# Multi-Function_Expander.net
KiCad netlist of a schematic drawn in Altium Designer
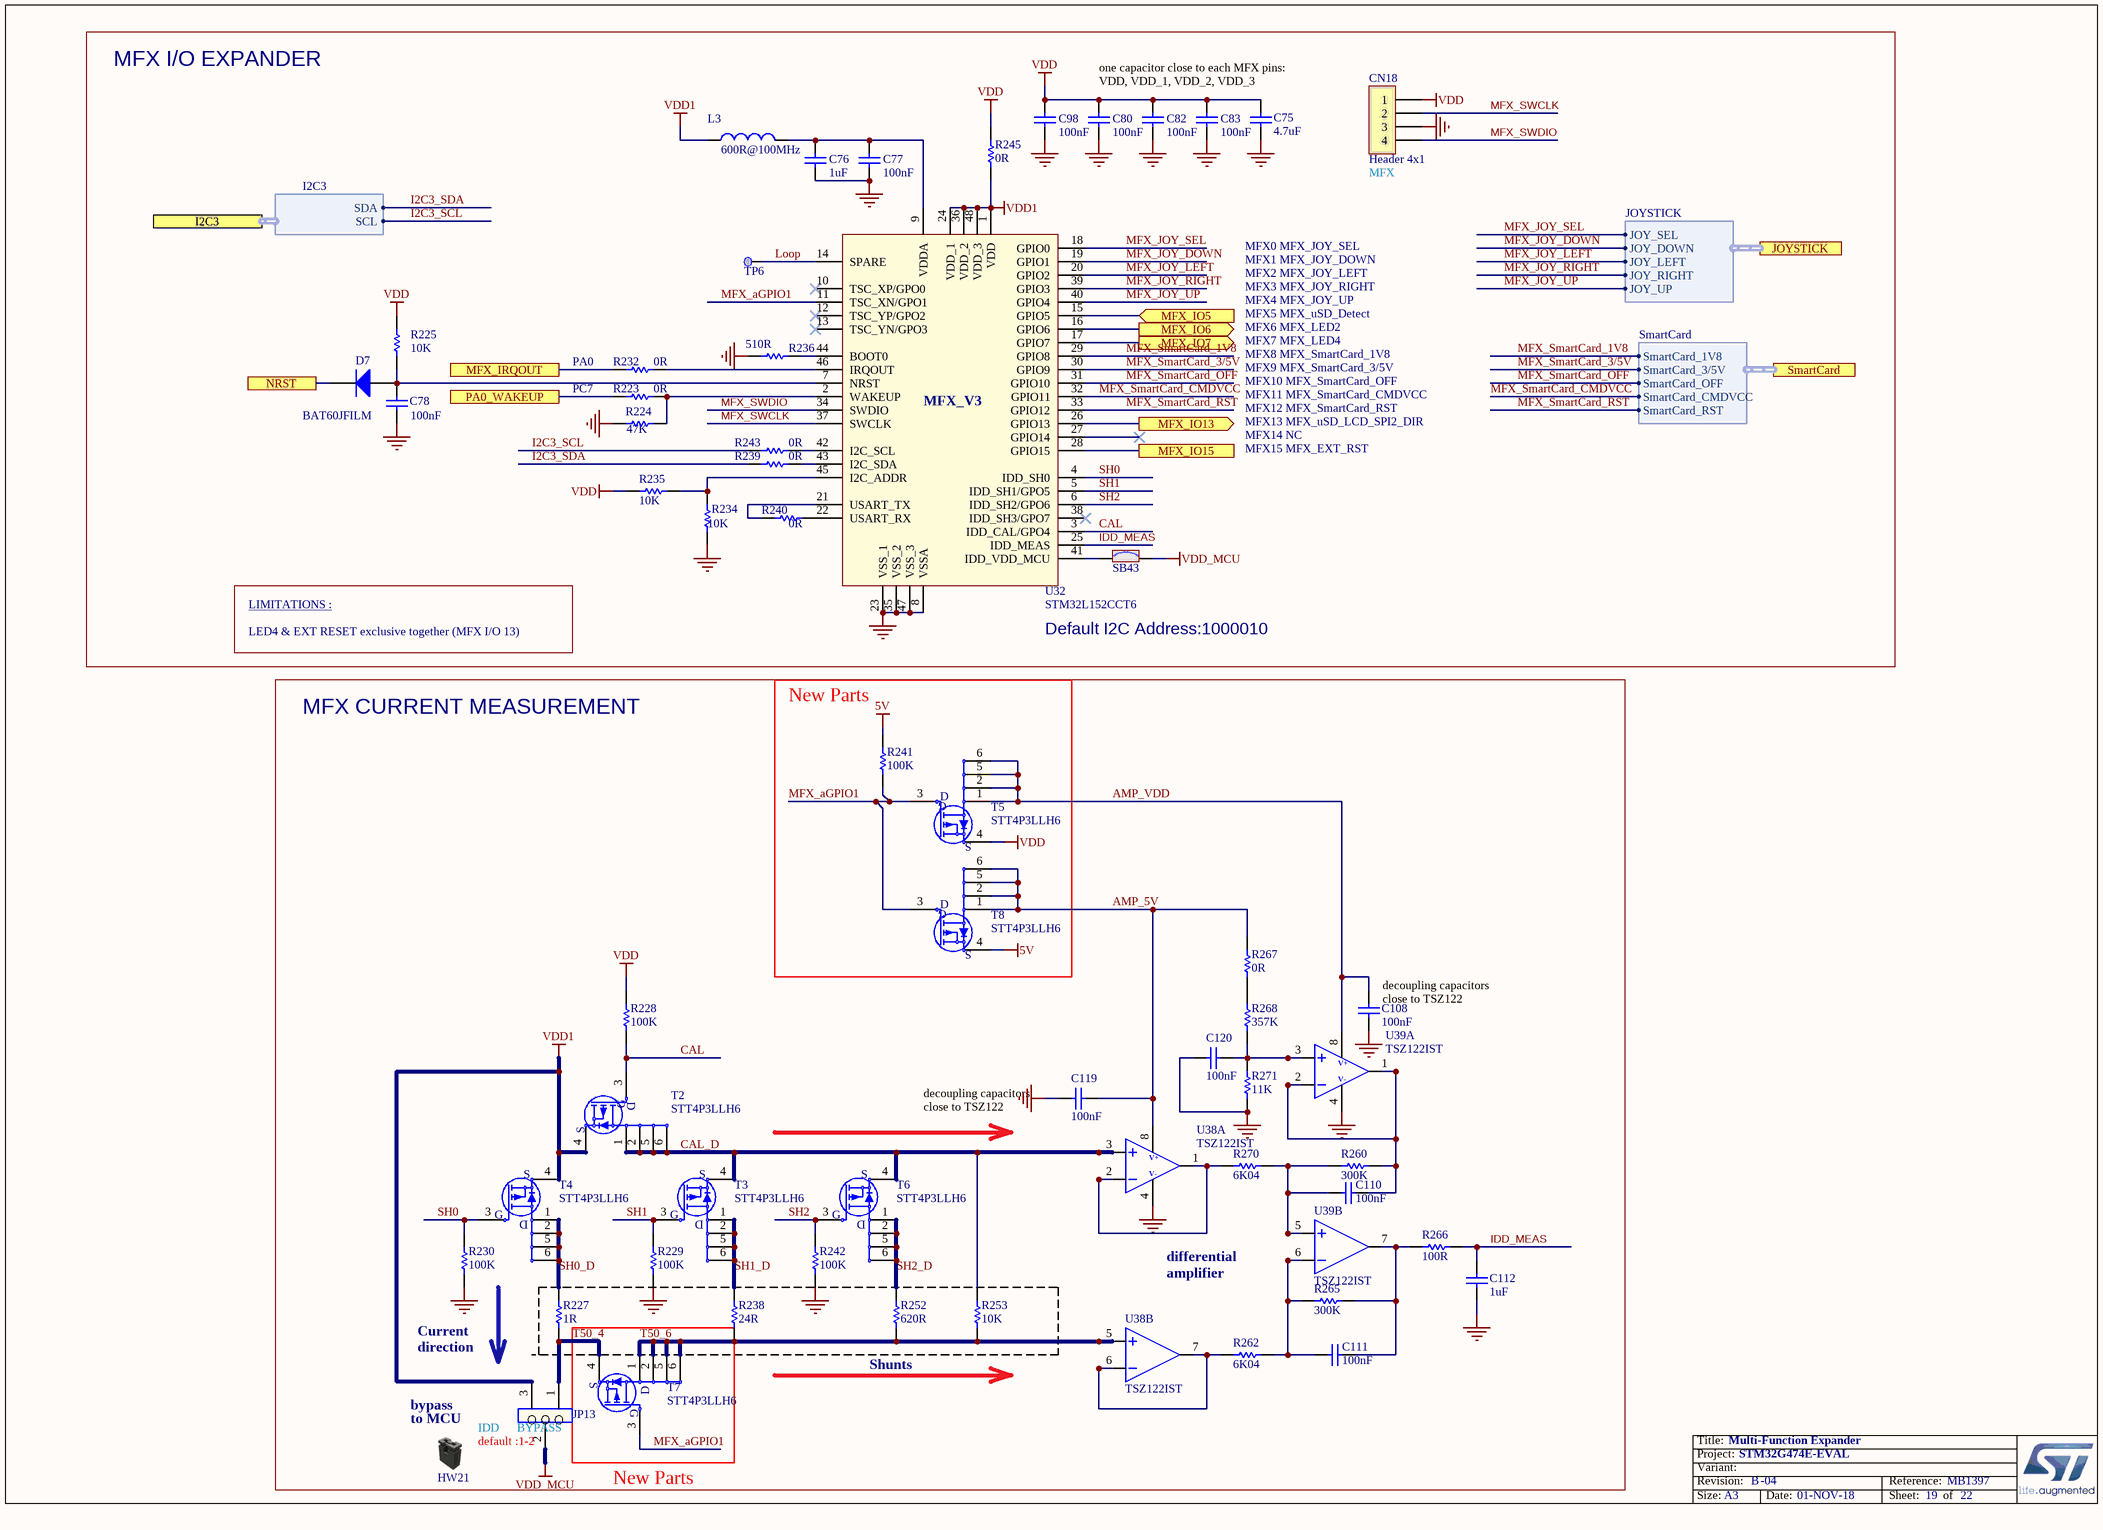
[diagram p0: Multi-Function Expander.SchDoc]

(export (version "E")
  (design (tool "Eeschema 10.0.6"))
  (components
    (comp (ref "C75")
      (value "4.7uF")
      (footprint "C0603")
      (description "Capacitor, MLCC, 4.7uF, 16V, X5R, 10%, 0603, T=0.8mm")
      (fields
        (field (name "INTERNAL_PART_NUMBER") "MCD-00009")
        (field (name "MANUFACTURER_PART_NUMBER") "CC0603KRX5R7BB475")
        (field (name "PROVIDED_BY") "SUBCO")
      )
      (libsource (lib "MCD_PARTS_database") (part "Capacitor"))
    )
    (comp (ref "C76")
      (value "1uF")
      (footprint "C0603")
      (description "Capacitor, MLCC, 1uF, 16V, X5R, 10%, 0603, T=0,8mm")
      (fields
        (field (name "INTERNAL_PART_NUMBER") "MCD-00010")
        (field (name "MANUFACTURER_PART_NUMBER") "CC0603KRX5R7BB105")
        (field (name "PROVIDED_BY") "SUBCO")
      )
      (libsource (lib "MCD_PARTS_database") (part "Capacitor"))
    )
    (comp (ref "C77")
      (value "100nF")
      (footprint "C0402")
      (description "Capacitor, MLCC, 100nF, 16V, X7R, 10%, 0402, T=0.5mm")
      (fields
        (field (name "INTERNAL_PART_NUMBER") "MCD-00006")
        (field (name "MANUFACTURER_PART_NUMBER") "CC0402KRX7R7BB104")
        (field (name "PROVIDED_BY") "SUBCO")
      )
      (libsource (lib "MCD_PARTS_database") (part "Capacitor"))
    )
    (comp (ref "C78")
      (value "100nF")
      (footprint "C0402")
      (description "Capacitor, MLCC, 100nF, 16V, X7R, 10%, 0402, T=0.5mm")
      (fields
        (field (name "INTERNAL_PART_NUMBER") "MCD-00006")
        (field (name "MANUFACTURER_PART_NUMBER") "CC0402KRX7R7BB104")
        (field (name "PROVIDED_BY") "SUBCO")
      )
      (libsource (lib "MCD_PARTS_database") (part "Capacitor"))
    )
    (comp (ref "C80")
      (value "100nF")
      (footprint "C0402")
      (description "Capacitor, MLCC, 100nF, 16V, X7R, 10%, 0402, T=0.5mm")
      (fields
        (field (name "INTERNAL_PART_NUMBER") "MCD-00006")
        (field (name "MANUFACTURER_PART_NUMBER") "CC0402KRX7R7BB104")
        (field (name "PROVIDED_BY") "SUBCO")
      )
      (libsource (lib "MCD_PARTS_database") (part "Capacitor"))
    )
    (comp (ref "C82")
      (value "100nF")
      (footprint "C0402")
      (description "Capacitor, MLCC, 100nF, 16V, X7R, 10%, 0402, T=0.5mm")
      (fields
        (field (name "INTERNAL_PART_NUMBER") "MCD-00006")
        (field (name "MANUFACTURER_PART_NUMBER") "CC0402KRX7R7BB104")
        (field (name "PROVIDED_BY") "SUBCO")
      )
      (libsource (lib "MCD_PARTS_database") (part "Capacitor"))
    )
    (comp (ref "C83")
      (value "100nF")
      (footprint "C0402")
      (description "Capacitor, MLCC, 100nF, 16V, X7R, 10%, 0402, T=0.5mm")
      (fields
        (field (name "INTERNAL_PART_NUMBER") "MCD-00006")
        (field (name "MANUFACTURER_PART_NUMBER") "CC0402KRX7R7BB104")
        (field (name "PROVIDED_BY") "SUBCO")
      )
      (libsource (lib "MCD_PARTS_database") (part "Capacitor"))
    )
    (comp (ref "C98")
      (value "100nF")
      (footprint "C0402")
      (description "Capacitor, MLCC, 100nF, 16V, X7R, 10%, 0402, T=0.5mm")
      (fields
        (field (name "INTERNAL_PART_NUMBER") "MCD-00006")
        (field (name "MANUFACTURER_PART_NUMBER") "CC0402KRX7R7BB104")
        (field (name "PROVIDED_BY") "SUBCO")
      )
      (libsource (lib "MCD_PARTS_database") (part "Capacitor"))
    )
    (comp (ref "C108")
      (value "100nF")
      (footprint "C0603")
      (description "Capacitor, MLCC, 100nF, 16V, X7R, 10%, 0603, T=0,8mm")
      (fields
        (field (name "INTERNAL_PART_NUMBER") "MCD-00211")
        (field (name "MANUFACTURER_PART_NUMBER") "CC0603KRX7R7BB104")
        (field (name "PROVIDED_BY") "SUBCO")
      )
      (libsource (lib "MCD_PARTS_database") (part "Capacitor"))
    )
    (comp (ref "C110")
      (value "100nF")
      (footprint "C0603")
      (description "Capacitor, MLCC, 100nF, 16V, X7R, 10%, 0603, T=0,8mm")
      (fields
        (field (name "INTERNAL_PART_NUMBER") "MCD-00211")
        (field (name "MANUFACTURER_PART_NUMBER") "CC0603KRX7R7BB104")
        (field (name "PROVIDED_BY") "SUBCO")
      )
      (libsource (lib "MCD_PARTS_database") (part "Capacitor"))
    )
    (comp (ref "C111")
      (value "100nF")
      (footprint "C0603")
      (description "Capacitor, MLCC, 100nF, 16V, X7R, 10%, 0603, T=0,8mm")
      (fields
        (field (name "INTERNAL_PART_NUMBER") "MCD-00211")
        (field (name "MANUFACTURER_PART_NUMBER") "CC0603KRX7R7BB104")
        (field (name "PROVIDED_BY") "SUBCO")
      )
      (libsource (lib "MCD_PARTS_database") (part "Capacitor"))
    )
    (comp (ref "C112")
      (value "1uF")
      (footprint "C0603")
      (description "Capacitor, MLCC, 1uF, 16V, X5R, 10%, 0603, T=0,8mm")
      (fields
        (field (name "INTERNAL_PART_NUMBER") "MCD-00010")
        (field (name "MANUFACTURER_PART_NUMBER") "CC0603KRX5R7BB105")
        (field (name "PROVIDED_BY") "SUBCO")
      )
      (libsource (lib "MCD_PARTS_database") (part "Capacitor"))
    )
    (comp (ref "C119")
      (value "100nF")
      (footprint "C0603")
      (description "Capacitor, MLCC, 100nF, 16V, X7R, 10%, 0603, T=0,8mm")
      (fields
        (field (name "INTERNAL_PART_NUMBER") "MCD-00211")
        (field (name "MANUFACTURER_PART_NUMBER") "CC0603KRX7R7BB104")
        (field (name "PROVIDED_BY") "SUBCO")
      )
      (libsource (lib "MCD_PARTS_database") (part "Capacitor"))
    )
    (comp (ref "C120")
      (value "100nF")
      (footprint "C0603")
      (description "Capacitor, MLCC, 100nF, 16V, X7R, 10%, 0603, T=0,8mm")
      (fields
        (field (name "INTERNAL_PART_NUMBER") "MCD-00211")
        (field (name "MANUFACTURER_PART_NUMBER") "CC0603KRX7R7BB104")
        (field (name "PROVIDED_BY") "SUBCO")
      )
      (libsource (lib "MCD_PARTS_database") (part "Capacitor"))
    )
    (comp (ref "CN18")
      (value "Header 4x1")
      (footprint "CON_SAMTEC_TSW-104-07-G-S")
      (description "Header, 4x1, 2,54mm, VR, TH, Height 5.84mm/2.54mm")
      (fields
        (field (name "INTERNAL_PART_NUMBER") "MCD-00029")
        (field (name "MANUFACTURER_PART_NUMBER") "TSW-104-07-x-S")
        (field (name "PROVIDED_BY") "SUBCO")
      )
      (libsource (lib "MCD_PARTS_database") (part "Header 4x1"))
    )
    (comp (ref "D7")
      (value "BAT60JFILM")
      (footprint "DIO_SOD323")
      (fields
        (field (name "INTERNAL_PART_NUMBER") "MCD-00034")
        (field (name "MANUFACTURER") "STMICROELECTRONICS")
        (field (name "BMS_PART_NUMBER") "9151097")
        (field (name "PROVIDED_BY") "SUBCO with ST control")
      )
      (libsource (lib "MCD_PARTS_database") (part "BAT60JFILM"))
    )
    (comp (ref "HW21")
      (value "Shunt Black 2.54mm")
      (description "SHUNT 2.54mm BLACK")
      (fields
        (field (name "INTERNAL_PART_NUMBER") "MCD-00043")
        (field (name "MANUFACTURER_PART_NUMBER") "SNT-100-BK-G")
        (field (name "PROVIDED_BY") "SUBCO")
      )
      (libsource (lib "MCD_PARTS_database") (part "Shunt Black 2.54mm"))
    )
    (comp (ref "JP13")
      (value "Jumper_Header 3x1")
      (footprint "CON_SAMTEC_TSW-103-07-F-S")
      (description "Header, 3x1, 2,54mm, VR, TH, Height 5.84mm/2.54mm")
      (fields
        (field (name "INTERNAL_PART_NUMBER") "MCD-00111")
        (field (name "MANUFACTURER_PART_NUMBER") "TSW-103-07-F-S")
        (field (name "PROVIDED_BY") "SUBCO")
      )
      (libsource (lib "MCD_PARTS_database") (part "Jumper_Header 3x1"))
    )
    (comp (ref "L3")
      (value "600R@100MHz")
      (footprint "L0603")
      (description "SMD Chip ferrite bead, 600R@100MHz +/-25%, 350mA, 500mohm DC, 0603, T=0.8mm")
      (fields
        (field (name "INTERNAL_PART_NUMBER") "MCD-00047")
        (field (name "MANUFACTURER_PART_NUMBER") "FCM1608KF-601T03")
        (field (name "PROVIDED_BY") "SUBCO")
      )
      (libsource (lib "MCD_PARTS_database") (part "BEAD"))
    )
    (comp (ref "R223")
      (value "0R")
      (footprint "R0603")
      (description "Resistor,0R,0603,5%,1/10W")
      (fields
        (field (name "INTERNAL_PART_NUMBER") "MCD-00056")
        (field (name "MANUFACTURER_PART_NUMBER") "RC0603JR-070RL")
        (field (name "PROVIDED_BY") "SUBCO")
      )
      (libsource (lib "MCD_PARTS_database") (part "Resistor"))
    )
    (comp (ref "R224")
      (value "47K")
      (footprint "R0402")
      (description "Resistor,47K,0402,1%,1/16W")
      (fields
        (field (name "INTERNAL_PART_NUMBER") "MCD-00063")
        (field (name "MANUFACTURER_PART_NUMBER") "RC0402FR-0747KL")
        (field (name "PROVIDED_BY") "SUBCO")
      )
      (libsource (lib "MCD_PARTS_database") (part "Resistor"))
    )
    (comp (ref "R225")
      (value "10K")
      (footprint "R0402")
      (description "Resistor,10K,0402,1%,1/16W")
      (fields
        (field (name "INTERNAL_PART_NUMBER") "MCD-00053")
        (field (name "MANUFACTURER_PART_NUMBER") "RC0402FR-0710KL")
        (field (name "PROVIDED_BY") "SUBCO")
      )
      (libsource (lib "MCD_PARTS_database") (part "Resistor"))
    )
    (comp (ref "R227")
      (value "1R")
      (footprint "R0805")
      (description "Resistor, 1R, 0805, 1%, 1/8W")
      (fields
        (field (name "INTERNAL_PART_NUMBER") "MCD-00323")
        (field (name "MANUFACTURER_PART_NUMBER") "RC0805FR-071RL")
        (field (name "PROVIDED_BY") "SUBCO")
      )
      (libsource (lib "MCD_PARTS_database") (part "Resistor"))
    )
    (comp (ref "R228")
      (value "100K")
      (footprint "R0603")
      (description "Resistor,100K,0603,1%,1/10W")
      (fields
        (field (name "INTERNAL_PART_NUMBER") "MCD-00223")
        (field (name "MANUFACTURER_PART_NUMBER") "RC0603FR-07100KL")
        (field (name "PROVIDED_BY") "SUBCO")
      )
      (libsource (lib "MCD_PARTS_database") (part "Resistor"))
    )
    (comp (ref "R229")
      (value "100K")
      (footprint "R0603")
      (description "Resistor,100K,0603,1%,1/10W")
      (fields
        (field (name "INTERNAL_PART_NUMBER") "MCD-00223")
        (field (name "MANUFACTURER_PART_NUMBER") "RC0603FR-07100KL")
        (field (name "PROVIDED_BY") "SUBCO")
      )
      (libsource (lib "MCD_PARTS_database") (part "Resistor"))
    )
    (comp (ref "R230")
      (value "100K")
      (footprint "R0603")
      (description "Resistor,100K,0603,1%,1/10W")
      (fields
        (field (name "INTERNAL_PART_NUMBER") "MCD-00223")
        (field (name "MANUFACTURER_PART_NUMBER") "RC0603FR-07100KL")
        (field (name "PROVIDED_BY") "SUBCO")
      )
      (libsource (lib "MCD_PARTS_database") (part "Resistor"))
    )
    (comp (ref "R232")
      (value "0R")
      (footprint "R0603")
      (description "Resistor,0R,0603,5%,1/10W")
      (fields
        (field (name "INTERNAL_PART_NUMBER") "MCD-00056")
        (field (name "MANUFACTURER_PART_NUMBER") "RC0603JR-070RL")
        (field (name "PROVIDED_BY") "SUBCO")
      )
      (libsource (lib "MCD_PARTS_database") (part "Resistor"))
    )
    (comp (ref "R234")
      (value "10K")
      (footprint "R0402")
      (description "Resistor,10K,0402,1%,1/16W")
      (fields
        (field (name "INTERNAL_PART_NUMBER") "MCD-00053")
        (field (name "MANUFACTURER_PART_NUMBER") "RC0402FR-0710KL")
        (field (name "PROVIDED_BY") "SUBCO")
      )
      (libsource (lib "MCD_PARTS_database") (part "Resistor"))
    )
    (comp (ref "R235")
      (value "10K")
      (footprint "R0402")
      (description "Resistor,10K,0402,1%,1/16W")
      (fields
        (field (name "INTERNAL_PART_NUMBER") "MCD-00053")
        (field (name "MANUFACTURER_PART_NUMBER") "RC0402FR-0710KL")
        (field (name "PROVIDED_BY") "SUBCO")
      )
      (libsource (lib "MCD_PARTS_database") (part "Resistor"))
    )
    (comp (ref "R236")
      (value "510R")
      (footprint "R0402")
      (description "Resistor,510R,0402,1%,1/16W")
      (fields
        (field (name "INTERNAL_PART_NUMBER") "MCD-00064")
        (field (name "MANUFACTURER_PART_NUMBER") "RC0402FR-07510RL")
        (field (name "PROVIDED_BY") "SUBCO")
      )
      (libsource (lib "MCD_PARTS_database") (part "Resistor"))
    )
    (comp (ref "R238")
      (value "24R")
      (footprint "R0805")
      (description "Resistor,24R,0805,1%,1/8W")
      (fields
        (field (name "INTERNAL_PART_NUMBER") "MCD-01152")
        (field (name "MANUFACTURER_PART_NUMBER") "RC0805FR-0724RL")
        (field (name "PROVIDED_BY") "SUBCO")
      )
      (libsource (lib "MCD_PARTS_database") (part "Resistor"))
    )
    (comp (ref "R239")
      (value "0R")
      (footprint "R0402")
      (description "Resistor,0R,0402,5%,1/16W")
      (fields
        (field (name "INTERNAL_PART_NUMBER") "MCD-00052")
        (field (name "MANUFACTURER_PART_NUMBER") "RC0402JR-070RL")
        (field (name "PROVIDED_BY") "SUBCO")
      )
      (libsource (lib "MCD_PARTS_database") (part "Resistor"))
    )
    (comp (ref "R240")
      (value "0R")
      (footprint "R0603")
      (description "Resistor,0R,0603,5%,1/10W")
      (fields
        (field (name "INTERNAL_PART_NUMBER") "MCD-00056")
        (field (name "MANUFACTURER_PART_NUMBER") "RC0603JR-070RL")
        (field (name "PROVIDED_BY") "SUBCO")
      )
      (libsource (lib "MCD_PARTS_database") (part "Resistor"))
    )
    (comp (ref "R241")
      (value "100K")
      (footprint "R0603")
      (description "Resistor,100K,0603,1%,1/10W")
      (fields
        (field (name "INTERNAL_PART_NUMBER") "MCD-00223")
        (field (name "MANUFACTURER_PART_NUMBER") "RC0603FR-07100KL")
        (field (name "PROVIDED_BY") "SUBCO")
      )
      (libsource (lib "MCD_PARTS_database") (part "Resistor"))
    )
    (comp (ref "R242")
      (value "100K")
      (footprint "R0603")
      (description "Resistor,100K,0603,1%,1/10W")
      (fields
        (field (name "INTERNAL_PART_NUMBER") "MCD-00223")
        (field (name "MANUFACTURER_PART_NUMBER") "RC0603FR-07100KL")
        (field (name "PROVIDED_BY") "SUBCO")
      )
      (libsource (lib "MCD_PARTS_database") (part "Resistor"))
    )
    (comp (ref "R243")
      (value "0R")
      (footprint "R0402")
      (description "Resistor,0R,0402,5%,1/16W")
      (fields
        (field (name "INTERNAL_PART_NUMBER") "MCD-00052")
        (field (name "MANUFACTURER_PART_NUMBER") "RC0402JR-070RL")
        (field (name "PROVIDED_BY") "SUBCO")
      )
      (libsource (lib "MCD_PARTS_database") (part "Resistor"))
    )
    (comp (ref "R245")
      (value "0R")
      (footprint "R0603")
      (description "Resistor,0R,0603,5%,1/10W")
      (fields
        (field (name "INTERNAL_PART_NUMBER") "MCD-00056")
        (field (name "MANUFACTURER_PART_NUMBER") "RC0603JR-070RL")
        (field (name "PROVIDED_BY") "SUBCO")
      )
      (libsource (lib "MCD_PARTS_database") (part "Resistor"))
    )
    (comp (ref "R252")
      (value "620R")
      (footprint "R0805")
      (description "Resistor,620R,0805,1%,1/8W")
      (fields
        (field (name "INTERNAL_PART_NUMBER") "MCD-01153")
        (field (name "MANUFACTURER_PART_NUMBER") "RC0805FR-07620RL")
        (field (name "PROVIDED_BY") "SUBCO")
      )
      (libsource (lib "MCD_PARTS_database") (part "Resistor"))
    )
    (comp (ref "R253")
      (value "10K")
      (footprint "R0805")
      (description "Resistor,10K,0805,1%,1/8W")
      (fields
        (field (name "INTERNAL_PART_NUMBER") "MCD-01154")
        (field (name "MANUFACTURER_PART_NUMBER") "RC0805FR-0710KL")
        (field (name "PROVIDED_BY") "SUBCO")
      )
      (libsource (lib "MCD_PARTS_database") (part "Resistor"))
    )
    (comp (ref "R260")
      (value "300K")
      (footprint "R0603")
      (description "Resistor,300K,0603,1%,1/10W")
      (fields
        (field (name "INTERNAL_PART_NUMBER") "MCD-00454")
        (field (name "MANUFACTURER_PART_NUMBER") "RC0603FR-07300KL")
        (field (name "PROVIDED_BY") "SUBCO")
      )
      (libsource (lib "MCD_PARTS_database") (part "Resistor"))
    )
    (comp (ref "R262")
      (value "6K04")
      (footprint "R0603")
      (description "Resistor,6K04,0603,1%,1/10W")
      (fields
        (field (name "INTERNAL_PART_NUMBER") "MCD-01151")
        (field (name "MANUFACTURER_PART_NUMBER") "RC0603FR-076K04L")
        (field (name "PROVIDED_BY") "SUBCO")
      )
      (libsource (lib "MCD_PARTS_database") (part "Resistor"))
    )
    (comp (ref "R265")
      (value "300K")
      (footprint "R0603")
      (description "Resistor,300K,0603,1%,1/10W")
      (fields
        (field (name "INTERNAL_PART_NUMBER") "MCD-00454")
        (field (name "MANUFACTURER_PART_NUMBER") "RC0603FR-07300KL")
        (field (name "PROVIDED_BY") "SUBCO")
      )
      (libsource (lib "MCD_PARTS_database") (part "Resistor"))
    )
    (comp (ref "R266")
      (value "100R")
      (footprint "R0402")
      (description "Resistor,100R,0402,1%,1/16W")
      (fields
        (field (name "INTERNAL_PART_NUMBER") "MCD-00119")
        (field (name "MANUFACTURER_PART_NUMBER") "RC0402FR-07100RL")
        (field (name "PROVIDED_BY") "SUBCO")
      )
      (libsource (lib "MCD_PARTS_database") (part "Resistor"))
    )
    (comp (ref "R267")
      (value "0R")
      (footprint "R0603")
      (description "Resistor,0R,0603,5%,1/10W")
      (fields
        (field (name "INTERNAL_PART_NUMBER") "MCD-00056")
        (field (name "MANUFACTURER_PART_NUMBER") "RC0603JR-070RL")
        (field (name "PROVIDED_BY") "SUBCO")
      )
      (libsource (lib "MCD_PARTS_database") (part "Resistor"))
    )
    (comp (ref "R268")
      (value "357K")
      (footprint "R0603")
      (description "Resistor,357K,0603,1%,1/10W")
      (fields
        (field (name "INTERNAL_PART_NUMBER") "MCD-01150")
        (field (name "MANUFACTURER_PART_NUMBER") "RC0603FR-07357KL")
        (field (name "PROVIDED_BY") "SUBCO")
      )
      (libsource (lib "MCD_PARTS_database") (part "Resistor"))
    )
    (comp (ref "R270")
      (value "6K04")
      (footprint "R0603")
      (description "Resistor,6K04,0603,1%,1/10W")
      (fields
        (field (name "INTERNAL_PART_NUMBER") "MCD-01151")
        (field (name "MANUFACTURER_PART_NUMBER") "RC0603FR-076K04L")
        (field (name "PROVIDED_BY") "SUBCO")
      )
      (libsource (lib "MCD_PARTS_database") (part "Resistor"))
    )
    (comp (ref "R271")
      (value "11K")
      (footprint "R0603")
      (description "Resistor,11K,0603,1%,1/10W")
      (fields
        (field (name "INTERNAL_PART_NUMBER") "MCD-00366")
        (field (name "MANUFACTURER_PART_NUMBER") "RC0603FR-0711KL")
        (field (name "PROVIDED_BY") "SUBCO")
      )
      (libsource (lib "MCD_PARTS_database") (part "Resistor"))
    )
    (comp (ref "SB43")
      (value "SB_ON")
      (footprint "SOLDER-BRIDGE_R0603-0R")
      (description "Solder Bridge ON")
      (fields
        (field (name "INTERNAL_PART_NUMBER") "MCD-00071")
        (field (name "MANUFACTURER_PART_NUMBER") "RC0603JR-070RL")
        (field (name "PROVIDED_BY") "SUBCO")
      )
      (libsource (lib "MCD_PARTS_database") (part "SB_ON"))
    )
    (comp (ref "T2")
      (value "STT4P3LLH6")
      (footprint "MOS_SOT23-6L")
      (description "Power MOSFET - P-Channel 30 V, 0.048 ? typ., 4 A STripFET H6 DeepGATE - SOT23-6L")
      (fields
        (field (name "INTERNAL_PART_NUMBER") "MCD-00574")
        (field (name "MANUFACTURER") "STMICROELECTRONICS")
        (field (name "PROVIDED_BY") "SUBCO with ST control")
      )
      (libsource (lib "MCD_PARTS_database") (part "STT4P3LLH6"))
    )
    (comp (ref "T3")
      (value "STT4P3LLH6")
      (footprint "MOS_SOT23-6L")
      (description "Power MOSFET - P-Channel 30 V, 0.048 ? typ., 4 A STripFET H6 DeepGATE - SOT23-6L")
      (fields
        (field (name "INTERNAL_PART_NUMBER") "MCD-00574")
        (field (name "MANUFACTURER") "STMICROELECTRONICS")
        (field (name "PROVIDED_BY") "SUBCO with ST control")
      )
      (libsource (lib "MCD_PARTS_database") (part "STT4P3LLH6"))
    )
    (comp (ref "T4")
      (value "STT4P3LLH6")
      (footprint "MOS_SOT23-6L")
      (description "Power MOSFET - P-Channel 30 V, 0.048 ? typ., 4 A STripFET H6 DeepGATE - SOT23-6L")
      (fields
        (field (name "INTERNAL_PART_NUMBER") "MCD-00574")
        (field (name "MANUFACTURER") "STMICROELECTRONICS")
        (field (name "PROVIDED_BY") "SUBCO with ST control")
      )
      (libsource (lib "MCD_PARTS_database") (part "STT4P3LLH6"))
    )
    (comp (ref "T5")
      (value "STT4P3LLH6")
      (footprint "MOS_SOT23-6L")
      (description "Power MOSFET - P-Channel 30 V, 0.048 ? typ., 4 A STripFET H6 DeepGATE - SOT23-6L")
      (fields
        (field (name "INTERNAL_PART_NUMBER") "MCD-00574")
        (field (name "MANUFACTURER") "STMICROELECTRONICS")
        (field (name "PROVIDED_BY") "SUBCO with ST control")
      )
      (libsource (lib "MCD_PARTS_database") (part "STT4P3LLH6"))
    )
    (comp (ref "T6")
      (value "STT4P3LLH6")
      (footprint "MOS_SOT23-6L")
      (description "Power MOSFET - P-Channel 30 V, 0.048 ? typ., 4 A STripFET H6 DeepGATE - SOT23-6L")
      (fields
        (field (name "INTERNAL_PART_NUMBER") "MCD-00574")
        (field (name "MANUFACTURER") "STMICROELECTRONICS")
        (field (name "PROVIDED_BY") "SUBCO with ST control")
      )
      (libsource (lib "MCD_PARTS_database") (part "STT4P3LLH6"))
    )
    (comp (ref "T7")
      (value "STT4P3LLH6")
      (footprint "MOS_SOT23-6L")
      (description "Power MOSFET - P-Channel 30 V, 0.048 ? typ., 4 A STripFET H6 DeepGATE - SOT23-6L")
      (fields
        (field (name "INTERNAL_PART_NUMBER") "MCD-00574")
        (field (name "MANUFACTURER") "STMICROELECTRONICS")
        (field (name "PROVIDED_BY") "SUBCO with ST control")
      )
      (libsource (lib "MCD_PARTS_database") (part "STT4P3LLH6"))
    )
    (comp (ref "T8")
      (value "STT4P3LLH6")
      (footprint "MOS_SOT23-6L")
      (description "Power MOSFET - P-Channel 30 V, 0.048 ? typ., 4 A STripFET H6 DeepGATE - SOT23-6L")
      (fields
        (field (name "INTERNAL_PART_NUMBER") "MCD-00574")
        (field (name "MANUFACTURER") "STMICROELECTRONICS")
        (field (name "PROVIDED_BY") "SUBCO with ST control")
      )
      (libsource (lib "MCD_PARTS_database") (part "STT4P3LLH6"))
    )
    (comp (ref "TP6")
      (value "Test Point")
      (footprint "TP_SMD_1MM")
      (description "Test Point 1mm")
      (fields (field (name "INTERNAL_PART_NUMBER") "MCD-00074") (field (name "MANUFACTURER") "n/a"))
      (libsource (lib "MCD_PARTS_database") (part "Test Point"))
    )
    (comp (ref "U32")
      (value "STM32L152CCT6")
      (footprint "ICC_LQFP48_7X7_P050")
      (description "Ultra-low-power 32-bit MCU ARM")
      (fields
        (field (name "INTERNAL_PART_NUMBER") "MCD-00135")
        (field (name "MANUFACTURER") "STMICROELECTRONICS")
        (field (name "PROVIDED_BY") "SUBCO with ST control")
      )
      (libsource (lib "MCD_PARTS_database") (part "STM32L152CCT6"))
    )
    (comp (ref "U38")
      (value "TSZ122IST")
      (footprint "ICC_MINISO8_3X3_P065")
      (description "Very high accuracy (5 µV) zero drift micropower 5 V operational amplifiers")
      (fields
        (field (name "INTERNAL_PART_NUMBER") "MCD-00325")
        (field (name "MANUFACTURER") "STMICROELECTRONICS")
        (field (name "PROVIDED_BY") "SUBCO with ST control")
      )
      (libsource (lib "MCD_PARTS_database") (part "TSZ122IST"))
    )
    (comp (ref "U39")
      (value "TSZ122IST")
      (footprint "ICC_MINISO8_3X3_P065")
      (description "Very high accuracy (5 µV) zero drift micropower 5 V operational amplifiers")
      (fields
        (field (name "INTERNAL_PART_NUMBER") "MCD-00325")
        (field (name "MANUFACTURER") "STMICROELECTRONICS")
        (field (name "PROVIDED_BY") "SUBCO with ST control")
      )
      (libsource (lib "MCD_PARTS_database") (part "TSZ122IST"))
    )
  )
  (nets
    (net (code "4") (name "/AMP_5V") (class "Default")
      (node (ref "C119") (pin "2") (pinfunction "2_2") (pintype "passive"))
      (node (ref "R267") (pin "2") (pinfunction "2_2") (pintype "passive"))
      (node (ref "T8") (pin "1") (pinfunction "S_1") (pintype "passive"))
      (node (ref "T8") (pin "2") (pinfunction "S_2") (pintype "passive"))
      (node (ref "T8") (pin "5") (pinfunction "D_5") (pintype "passive"))
      (node (ref "T8") (pin "6") (pinfunction "D_6") (pintype "passive"))
      (node (ref "U38") (pin "8") (pintype "passive"))
    )
    (net (code "5") (name "/AMP_VDD") (class "Default")
      (node (ref "C108") (pin "2") (pinfunction "2_2") (pintype "passive"))
      (node (ref "T5") (pin "1") (pinfunction "S_1") (pintype "passive"))
      (node (ref "T5") (pin "2") (pinfunction "S_2") (pintype "passive"))
      (node (ref "T5") (pin "5") (pinfunction "D_5") (pintype "passive"))
      (node (ref "T5") (pin "6") (pinfunction "D_6") (pintype "passive"))
      (node (ref "U39") (pin "8") (pintype "passive"))
    )
    (net (code "6") (name "/CAL") (class "Default")
      (node (ref "R228") (pin "1") (pinfunction "1_1") (pintype "passive"))
      (node (ref "T2") (pin "3") (pinfunction "G_3") (pintype "passive"))
      (node (ref "U32") (pin "3") (pinfunction "IDD_CAL/GPO4_3") (pintype "passive"))
    )
    (net (code "7") (name "/CAL_D") (class "Default")
      (node (ref "R253") (pin "2") (pinfunction "2_2") (pintype "passive"))
      (node (ref "T2") (pin "1") (pinfunction "S_1") (pintype "passive"))
      (node (ref "T2") (pin "2") (pinfunction "S_2") (pintype "passive"))
      (node (ref "T2") (pin "5") (pinfunction "D_5") (pintype "passive"))
      (node (ref "T2") (pin "6") (pinfunction "D_6") (pintype "passive"))
      (node (ref "T3") (pin "4") (pinfunction "S_4") (pintype "passive"))
      (node (ref "T6") (pin "4") (pinfunction "S_4") (pintype "passive"))
      (node (ref "U38") (pin "3") (pintype "passive"))
    )
    (net (code "8") (name "/I2C3_SCL") (class "Default")
      (node (ref "R243") (pin "1") (pinfunction "1_1") (pintype "passive"))
    )
    (net (code "9") (name "/I2C3_SDA") (class "Default")
      (node (ref "R239") (pin "1") (pinfunction "1_1") (pintype "passive"))
    )
    (net (code "10") (name "/IDD_MEAS") (class "Default")
      (node (ref "C112") (pin "2") (pinfunction "2_2") (pintype "passive"))
      (node (ref "R266") (pin "2") (pinfunction "2_2") (pintype "passive"))
      (node (ref "U32") (pin "25") (pinfunction "IDD_MEAS_25") (pintype "passive"))
    )
    (net (code "11") (name "/Loop") (class "Default")
      (node (ref "TP6") (pin "1") (pinfunction "1_1") (pintype "passive"))
      (node (ref "U32") (pin "14") (pinfunction "SPARE_14") (pintype "passive"))
    )
    (net (code "12") (name "/MFX_IO5") (class "Default")
      (node (ref "U32") (pin "15") (pinfunction "GPIO5_15") (pintype "passive"))
    )
    (net (code "13") (name "/MFX_IO6") (class "Default")
      (node (ref "U32") (pin "16") (pinfunction "GPIO6_16") (pintype "passive"))
    )
    (net (code "14") (name "/MFX_IO7") (class "Default")
      (node (ref "U32") (pin "17") (pinfunction "GPIO7_17") (pintype "passive"))
    )
    (net (code "15") (name "/MFX_IO13") (class "Default")
      (node (ref "U32") (pin "26") (pinfunction "GPIO13_26") (pintype "passive"))
    )
    (net (code "16") (name "/MFX_IO15") (class "Default")
      (node (ref "U32") (pin "28") (pinfunction "GPIO15_28") (pintype "passive"))
    )
    (net (code "17") (name "/MFX_IRQOUT") (class "Default")
      (node (ref "R232") (pin "1") (pinfunction "1_1") (pintype "passive"))
    )
    (net (code "18") (name "/MFX_JOY_DOWN") (class "Default")
      (node (ref "U32") (pin "19") (pinfunction "GPIO1_19") (pintype "passive"))
    )
    (net (code "19") (name "/MFX_JOY_LEFT") (class "Default")
      (node (ref "U32") (pin "20") (pinfunction "GPIO2_20") (pintype "passive"))
    )
    (net (code "20") (name "/MFX_JOY_RIGHT") (class "Default")
      (node (ref "U32") (pin "39") (pinfunction "GPIO3_39") (pintype "passive"))
    )
    (net (code "21") (name "/MFX_JOY_SEL") (class "Default")
      (node (ref "U32") (pin "18") (pinfunction "GPIO0_18") (pintype "passive"))
    )
    (net (code "22") (name "/MFX_JOY_UP") (class "Default")
      (node (ref "U32") (pin "40") (pinfunction "GPIO4_40") (pintype "passive"))
    )
    (net (code "23") (name "/MFX_SWCLK") (class "Default")
      (node (ref "CN18") (pin "2") (pinfunction "2_2") (pintype "passive"))
      (node (ref "U32") (pin "37") (pinfunction "SWCLK_37") (pintype "passive"))
    )
    (net (code "24") (name "/MFX_SWDIO") (class "Default")
      (node (ref "CN18") (pin "4") (pinfunction "4_4") (pintype "passive"))
      (node (ref "U32") (pin "34") (pinfunction "SWDIO_34") (pintype "passive"))
    )
    (net (code "25") (name "/MFX_SmartCard_1V8") (class "Default")
      (node (ref "U32") (pin "29") (pinfunction "GPIO8_29") (pintype "passive"))
    )
    (net (code "26") (name "/MFX_SmartCard_3{slash}5V") (class "Default")
      (node (ref "U32") (pin "30") (pinfunction "GPIO9_30") (pintype "passive"))
    )
    (net (code "27") (name "/MFX_SmartCard_CMDVCC") (class "Default")
      (node (ref "U32") (pin "32") (pinfunction "GPIO11_32") (pintype "passive"))
    )
    (net (code "28") (name "/MFX_SmartCard_OFF") (class "Default")
      (node (ref "U32") (pin "31") (pinfunction "GPIO10_31") (pintype "passive"))
    )
    (net (code "29") (name "/MFX_SmartCard_RST") (class "Default")
      (node (ref "U32") (pin "33") (pinfunction "GPIO12_33") (pintype "passive"))
    )
    (net (code "30") (name "/MFX_aGPIO1") (class "Default")
      (node (ref "R241") (pin "1") (pinfunction "1_1") (pintype "passive"))
      (node (ref "T5") (pin "3") (pinfunction "G_3") (pintype "passive"))
      (node (ref "T7") (pin "3") (pinfunction "G_3") (pintype "passive"))
      (node (ref "T8") (pin "3") (pinfunction "G_3") (pintype "passive"))
      (node (ref "U32") (pin "11") (pinfunction "TSC_XN/GPO1_11") (pintype "passive"))
    )
    (net (code "31") (name "/NRST") (class "Default")
      (node (ref "D7") (pin "2") (pinfunction "K_2") (pintype "passive"))
    )
    (net (code "32") (name "/PA0_WAKEUP") (class "Default")
      (node (ref "R223") (pin "2") (pinfunction "2_2") (pintype "passive"))
    )
    (net (code "33") (name "/SH0") (class "Default")
      (node (ref "R230") (pin "2") (pinfunction "2_2") (pintype "passive"))
      (node (ref "T4") (pin "3") (pinfunction "G_3") (pintype "passive"))
      (node (ref "U32") (pin "4") (pinfunction "IDD_SH0_4") (pintype "passive"))
    )
    (net (code "34") (name "/SH0_D") (class "Default")
      (node (ref "R227") (pin "2") (pinfunction "2_2") (pintype "passive"))
      (node (ref "T4") (pin "1") (pinfunction "S_1") (pintype "passive"))
      (node (ref "T4") (pin "2") (pinfunction "S_2") (pintype "passive"))
      (node (ref "T4") (pin "5") (pinfunction "D_5") (pintype "passive"))
      (node (ref "T4") (pin "6") (pinfunction "D_6") (pintype "passive"))
    )
    (net (code "35") (name "/SH1") (class "Default")
      (node (ref "R229") (pin "2") (pinfunction "2_2") (pintype "passive"))
      (node (ref "T3") (pin "3") (pinfunction "G_3") (pintype "passive"))
      (node (ref "U32") (pin "5") (pinfunction "IDD_SH1/GPO5_5") (pintype "passive"))
    )
    (net (code "36") (name "/SH1_D") (class "Default")
      (node (ref "R238") (pin "2") (pinfunction "2_2") (pintype "passive"))
      (node (ref "T3") (pin "1") (pinfunction "S_1") (pintype "passive"))
      (node (ref "T3") (pin "2") (pinfunction "S_2") (pintype "passive"))
      (node (ref "T3") (pin "5") (pinfunction "D_5") (pintype "passive"))
      (node (ref "T3") (pin "6") (pinfunction "D_6") (pintype "passive"))
    )
    (net (code "37") (name "/SH2") (class "Default")
      (node (ref "R242") (pin "2") (pinfunction "2_2") (pintype "passive"))
      (node (ref "T6") (pin "3") (pinfunction "G_3") (pintype "passive"))
      (node (ref "U32") (pin "6") (pinfunction "IDD_SH2/GPO6_6") (pintype "passive"))
    )
    (net (code "38") (name "/SH2_D") (class "Default")
      (node (ref "R252") (pin "2") (pinfunction "2_2") (pintype "passive"))
      (node (ref "T6") (pin "1") (pinfunction "S_1") (pintype "passive"))
      (node (ref "T6") (pin "2") (pinfunction "S_2") (pintype "passive"))
      (node (ref "T6") (pin "5") (pinfunction "D_5") (pintype "passive"))
      (node (ref "T6") (pin "6") (pinfunction "D_6") (pintype "passive"))
    )
    (net (code "39") (name "/T50_4") (class "Default")
      (node (ref "JP13") (pin "1") (pinfunction "1_1") (pintype "passive"))
      (node (ref "R227") (pin "1") (pinfunction "1_1") (pintype "passive"))
      (node (ref "T7") (pin "4") (pinfunction "S_4") (pintype "passive"))
    )
    (net (code "40") (name "/T50_6") (class "Default")
      (node (ref "R238") (pin "1") (pinfunction "1_1") (pintype "passive"))
      (node (ref "R252") (pin "1") (pinfunction "1_1") (pintype "passive"))
      (node (ref "R253") (pin "1") (pinfunction "1_1") (pintype "passive"))
      (node (ref "T7") (pin "1") (pinfunction "S_1") (pintype "passive"))
      (node (ref "T7") (pin "2") (pinfunction "S_2") (pintype "passive"))
      (node (ref "T7") (pin "5") (pinfunction "D_5") (pintype "passive"))
      (node (ref "T7") (pin "6") (pinfunction "D_6") (pintype "passive"))
      (node (ref "U38") (pin "5") (pintype "passive"))
    )
    (net (code "44") (name "5V") (class "Default")
      (node (ref "R241") (pin "2") (pinfunction "2_2") (pintype "passive"))
      (node (ref "T8") (pin "4") (pinfunction "S_4") (pintype "passive"))
    )
    (net (code "45") (name "GND") (class "Default")
      (node (ref "C108") (pin "1") (pinfunction "1_1") (pintype "passive"))
      (node (ref "C112") (pin "1") (pinfunction "1_1") (pintype "passive"))
      (node (ref "C119") (pin "1") (pinfunction "1_1") (pintype "passive"))
      (node (ref "C120") (pin "1") (pinfunction "1_1") (pintype "passive"))
      (node (ref "C75") (pin "1") (pinfunction "1_1") (pintype "passive"))
      (node (ref "C76") (pin "1") (pinfunction "1_1") (pintype "passive"))
      (node (ref "C77") (pin "1") (pinfunction "1_1") (pintype "passive"))
      (node (ref "C78") (pin "1") (pinfunction "1_1") (pintype "passive"))
      (node (ref "C80") (pin "1") (pinfunction "1_1") (pintype "passive"))
      (node (ref "C82") (pin "2") (pinfunction "2_2") (pintype "passive"))
      (node (ref "C83") (pin "1") (pinfunction "1_1") (pintype "passive"))
      (node (ref "C98") (pin "1") (pinfunction "1_1") (pintype "passive"))
      (node (ref "CN18") (pin "3") (pinfunction "3_3") (pintype "passive"))
      (node (ref "R224") (pin "1") (pinfunction "1_1") (pintype "passive"))
      (node (ref "R229") (pin "1") (pinfunction "1_1") (pintype "passive"))
      (node (ref "R230") (pin "1") (pinfunction "1_1") (pintype "passive"))
      (node (ref "R234") (pin "2") (pinfunction "2_2") (pintype "passive"))
      (node (ref "R236") (pin "2") (pinfunction "2_2") (pintype "passive"))
      (node (ref "R242") (pin "1") (pinfunction "1_1") (pintype "passive"))
      (node (ref "R271") (pin "1") (pinfunction "1_1") (pintype "passive"))
      (node (ref "U32") (pin "23") (pinfunction "VSS_1_23") (pintype "passive"))
      (node (ref "U32") (pin "35") (pinfunction "VSS_2_35") (pintype "passive"))
      (node (ref "U32") (pin "47") (pinfunction "VSS_3_47") (pintype "passive"))
      (node (ref "U32") (pin "8") (pinfunction "VSSA_8") (pintype "passive"))
      (node (ref "U38") (pin "4") (pintype "passive"))
      (node (ref "U39") (pin "4") (pintype "passive"))
    )
    (net (code "46") (name "Net-(C110-Pad1)") (class "Default")
      (node (ref "C110") (pin "1") (pinfunction "1_1") (pintype "passive"))
      (node (ref "R260") (pin "1") (pinfunction "1_1") (pintype "passive"))
      (node (ref "R270") (pin "2") (pinfunction "2_2") (pintype "passive"))
      (node (ref "U39") (pin "5") (pintype "passive"))
    )
    (net (code "47") (name "Net-(C110-Pad2)") (class "Default")
      (node (ref "C110") (pin "2") (pinfunction "2_2") (pintype "passive"))
      (node (ref "R260") (pin "2") (pinfunction "2_2") (pintype "passive"))
      (node (ref "U39") (pin "1") (pintype "passive"))
      (node (ref "U39") (pin "2") (pintype "passive"))
    )
    (net (code "48") (name "Net-(C111-Pad1)") (class "Default")
      (node (ref "C111") (pin "1") (pinfunction "1_1") (pintype "passive"))
      (node (ref "R262") (pin "2") (pinfunction "2_2") (pintype "passive"))
      (node (ref "R265") (pin "1") (pinfunction "1_1") (pintype "passive"))
      (node (ref "U39") (pin "6") (pintype "passive"))
    )
    (net (code "49") (name "Net-(C111-Pad2)") (class "Default")
      (node (ref "C111") (pin "2") (pinfunction "2_2") (pintype "passive"))
      (node (ref "R265") (pin "2") (pinfunction "2_2") (pintype "passive"))
      (node (ref "R266") (pin "1") (pinfunction "1_1") (pintype "passive"))
      (node (ref "U39") (pin "7") (pintype "passive"))
    )
    (net (code "50") (name "Net-(C120-Pad2)") (class "Default")
      (node (ref "C120") (pin "2") (pinfunction "2_2") (pintype "passive"))
      (node (ref "R268") (pin "1") (pinfunction "1_1") (pintype "passive"))
      (node (ref "R271") (pin "2") (pinfunction "2_2") (pintype "passive"))
      (node (ref "U39") (pin "3") (pintype "passive"))
    )
    (net (code "51") (name "Net-(D7-A)") (class "Default")
      (node (ref "C78") (pin "2") (pinfunction "2_2") (pintype "passive"))
      (node (ref "D7") (pin "1") (pinfunction "A_1") (pintype "passive"))
      (node (ref "R225") (pin "1") (pinfunction "1_1") (pintype "passive"))
      (node (ref "U32") (pin "7") (pinfunction "NRST_7") (pintype "passive"))
    )
    (net (code "52") (name "Net-(R262-Pad1)") (class "Default")
      (node (ref "R262") (pin "1") (pinfunction "1_1") (pintype "passive"))
      (node (ref "U38") (pin "6") (pintype "passive"))
      (node (ref "U38") (pin "7") (pintype "passive"))
    )
    (net (code "53") (name "Net-(R267-Pad1)") (class "Default")
      (node (ref "R267") (pin "1") (pinfunction "1_1") (pintype "passive"))
      (node (ref "R268") (pin "2") (pinfunction "2_2") (pintype "passive"))
    )
    (net (code "54") (name "Net-(R270-Pad1)") (class "Default")
      (node (ref "R270") (pin "1") (pinfunction "1_1") (pintype "passive"))
      (node (ref "U38") (pin "1") (pintype "passive"))
      (node (ref "U38") (pin "2") (pintype "passive"))
    )
    (net (code "55") (name "Net-(U32-BOOT0)") (class "Default")
      (node (ref "R236") (pin "1") (pinfunction "1_1") (pintype "passive"))
      (node (ref "U32") (pin "44") (pinfunction "BOOT0_44") (pintype "passive"))
    )
    (net (code "56") (name "Net-(U32-I2C_ADDR)") (class "Default")
      (node (ref "R234") (pin "1") (pinfunction "1_1") (pintype "passive"))
      (node (ref "R235") (pin "2") (pinfunction "2_2") (pintype "passive"))
      (node (ref "U32") (pin "45") (pinfunction "I2C_ADDR_45") (pintype "passive"))
    )
    (net (code "57") (name "Net-(U32-I2C_SCL)") (class "Default")
      (node (ref "R243") (pin "2") (pinfunction "2_2") (pintype "passive"))
      (node (ref "U32") (pin "42") (pinfunction "I2C_SCL_42") (pintype "passive"))
    )
    (net (code "58") (name "Net-(U32-I2C_SDA)") (class "Default")
      (node (ref "R239") (pin "2") (pinfunction "2_2") (pintype "passive"))
      (node (ref "U32") (pin "43") (pinfunction "I2C_SDA_43") (pintype "passive"))
    )
    (net (code "59") (name "Net-(U32-IDD_VDD_MCU)") (class "Default")
      (node (ref "SB43") (pin "1") (pinfunction "1_1") (pintype "passive"))
      (node (ref "U32") (pin "41") (pinfunction "IDD_VDD_MCU_41") (pintype "passive"))
    )
    (net (code "60") (name "Net-(U32-IRQOUT)") (class "Default")
      (node (ref "R232") (pin "2") (pinfunction "2_2") (pintype "passive"))
      (node (ref "U32") (pin "46") (pinfunction "IRQOUT_46") (pintype "passive"))
    )
    (net (code "61") (name "Net-(U32-USART_RX)") (class "Default")
      (node (ref "R240") (pin "2") (pinfunction "2_2") (pintype "passive"))
      (node (ref "U32") (pin "22") (pinfunction "USART_RX_22") (pintype "passive"))
    )
    (net (code "62") (name "Net-(U32-USART_TX)") (class "Default")
      (node (ref "R240") (pin "1") (pinfunction "1_1") (pintype "passive"))
      (node (ref "U32") (pin "21") (pinfunction "USART_TX_21") (pintype "passive"))
    )
    (net (code "63") (name "Net-(U32-VDDA)") (class "Default")
      (node (ref "C76") (pin "2") (pinfunction "2_2") (pintype "passive"))
      (node (ref "C77") (pin "2") (pinfunction "2_2") (pintype "passive"))
      (node (ref "L3") (pin "2") (pinfunction "2_2") (pintype "passive"))
      (node (ref "U32") (pin "9") (pinfunction "VDDA_9") (pintype "passive"))
    )
    (net (code "64") (name "Net-(U32-WAKEUP)") (class "Default")
      (node (ref "R223") (pin "1") (pinfunction "1_1") (pintype "passive"))
      (node (ref "R224") (pin "2") (pinfunction "2_2") (pintype "passive"))
      (node (ref "U32") (pin "2") (pinfunction "WAKEUP_2") (pintype "passive"))
    )
    (net (code "65") (name "VDD") (class "Default")
      (node (ref "C75") (pin "2") (pinfunction "2_2") (pintype "passive"))
      (node (ref "C80") (pin "2") (pinfunction "2_2") (pintype "passive"))
      (node (ref "C82") (pin "1") (pinfunction "1_1") (pintype "passive"))
      (node (ref "C83") (pin "2") (pinfunction "2_2") (pintype "passive"))
      (node (ref "C98") (pin "2") (pinfunction "2_2") (pintype "passive"))
      (node (ref "CN18") (pin "1") (pinfunction "1_1") (pintype "passive"))
      (node (ref "R225") (pin "2") (pinfunction "2_2") (pintype "passive"))
      (node (ref "R228") (pin "2") (pinfunction "2_2") (pintype "passive"))
      (node (ref "R235") (pin "1") (pinfunction "1_1") (pintype "passive"))
      (node (ref "R245") (pin "2") (pinfunction "2_2") (pintype "passive"))
      (node (ref "T5") (pin "4") (pinfunction "S_4") (pintype "passive"))
    )
    (net (code "66") (name "VDD1") (class "Default")
      (node (ref "JP13") (pin "3") (pinfunction "3_3") (pintype "passive"))
      (node (ref "L3") (pin "1") (pinfunction "1_1") (pintype "passive"))
      (node (ref "R245") (pin "1") (pinfunction "1_1") (pintype "passive"))
      (node (ref "T2") (pin "4") (pinfunction "S_4") (pintype "passive"))
      (node (ref "T4") (pin "4") (pinfunction "S_4") (pintype "passive"))
      (node (ref "U32") (pin "1") (pinfunction "VDD_1") (pintype "passive"))
      (node (ref "U32") (pin "24") (pinfunction "VDD_1_24") (pintype "passive"))
      (node (ref "U32") (pin "36") (pinfunction "VDD_2_36") (pintype "passive"))
      (node (ref "U32") (pin "48") (pinfunction "VDD_3_48") (pintype "passive"))
    )
    (net (code "67") (name "VDD_MCU") (class "Default")
      (node (ref "JP13") (pin "2") (pinfunction "2_2") (pintype "passive"))
      (node (ref "SB43") (pin "2") (pinfunction "2_2") (pintype "passive"))
    )
    (net (code "68") (name "unconnected-(U32-GPIO14-Pad27)") (class "Default")
      (node (ref "U32") (pin "27") (pinfunction "GPIO14_27") (pintype "passive+no_connect"))
    )
    (net (code "69") (name "unconnected-(U32-IDD_SH3{slash}GPO7-Pad38)") (class "Default")
      (node (ref "U32") (pin "38") (pinfunction "IDD_SH3/GPO7_38") (pintype "passive+no_connect"))
    )
    (net (code "70") (name "unconnected-(U32-TSC_XP{slash}GPO0-Pad10)") (class "Default")
      (node (ref "U32") (pin "10") (pinfunction "TSC_XP/GPO0_10") (pintype "passive+no_connect"))
    )
    (net (code "71") (name "unconnected-(U32-TSC_YN{slash}GPO3-Pad13)") (class "Default")
      (node (ref "U32") (pin "13") (pinfunction "TSC_YN/GPO3_13") (pintype "passive+no_connect"))
    )
    (net (code "72") (name "unconnected-(U32-TSC_YP{slash}GPO2-Pad12)") (class "Default")
      (node (ref "U32") (pin "12") (pinfunction "TSC_YP/GPO2_12") (pintype "passive+no_connect"))
    )
  )
)
